# pcm5102_dac.net
KiCad netlist of a schematic drawn in EAGLE
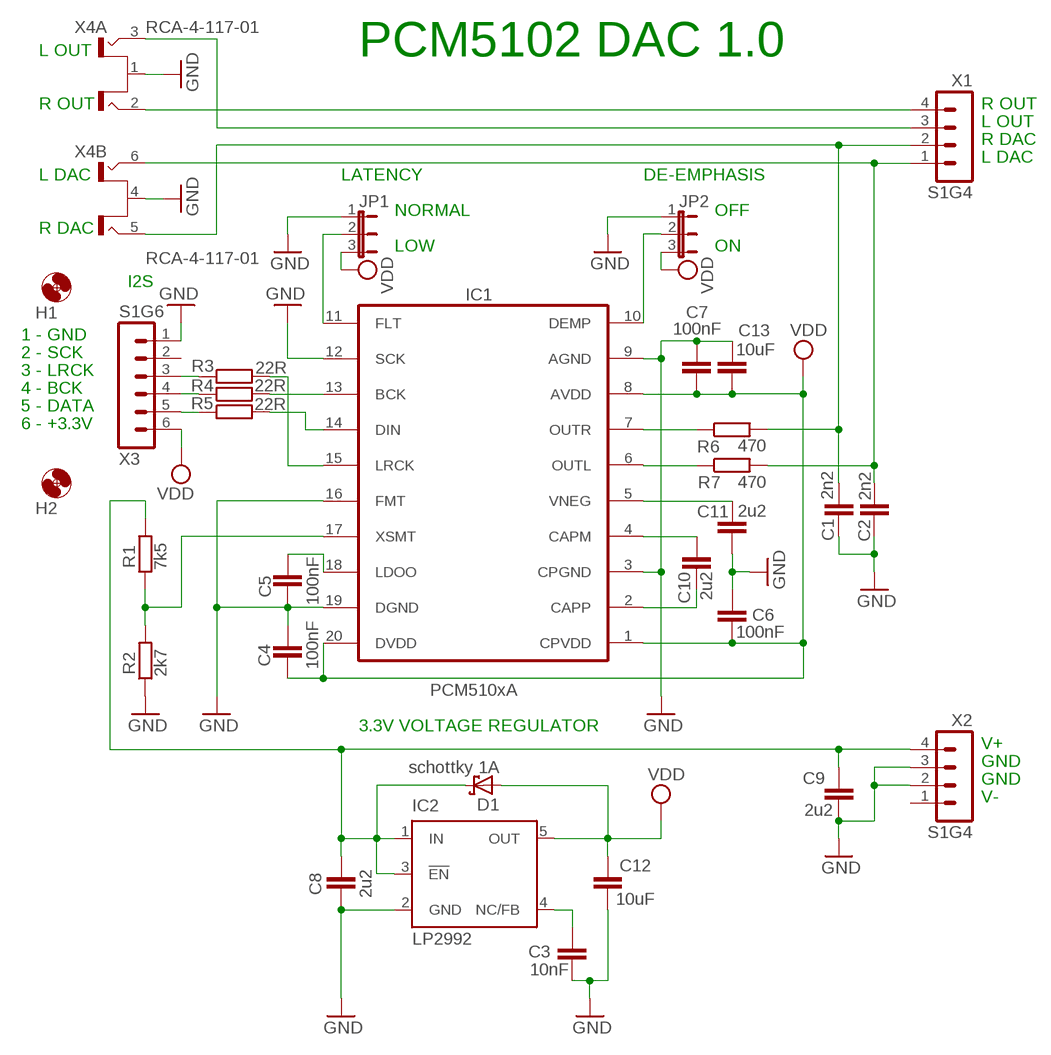
[diagram p0: schematic, sheet 1]

(export (version "E")
  (design (tool "Eeschema 10.0.6"))
  (components
    (comp (ref "C1")
      (value "2n2")
      (footprint "eagle-import:C1206")
      (libsource (lib "eagle-import") (part "C-EUC1206"))
    )
    (comp (ref "C2")
      (value "2n2")
      (footprint "eagle-import:C1206")
      (libsource (lib "eagle-import") (part "C-EUC1206"))
    )
    (comp (ref "C3")
      (value "10nF")
      (footprint "eagle-import:C1812")
      (libsource (lib "eagle-import") (part "C-EUC1812"))
    )
    (comp (ref "C4")
      (value "100nF")
      (footprint "eagle-import:C1206")
      (libsource (lib "eagle-import") (part "C-EUC1206"))
    )
    (comp (ref "C5")
      (value "100nF")
      (footprint "eagle-import:C1206")
      (libsource (lib "eagle-import") (part "C-EUC1206"))
    )
    (comp (ref "C6")
      (value "100nF")
      (footprint "eagle-import:C1206")
      (libsource (lib "eagle-import") (part "C-EUC1206"))
    )
    (comp (ref "C7")
      (value "100nF")
      (footprint "eagle-import:C1206")
      (libsource (lib "eagle-import") (part "C-EUC1206"))
    )
    (comp (ref "C8")
      (value "2u2")
      (footprint "eagle-import:C1206")
      (libsource (lib "eagle-import") (part "C-EUC1206"))
    )
    (comp (ref "C9")
      (value "2u2")
      (footprint "eagle-import:C1206")
      (libsource (lib "eagle-import") (part "C-EUC1206"))
    )
    (comp (ref "C10")
      (value "2u2")
      (footprint "eagle-import:C1206")
      (libsource (lib "eagle-import") (part "C-EUC1206"))
    )
    (comp (ref "C11")
      (value "2u2")
      (footprint "eagle-import:C1206")
      (libsource (lib "eagle-import") (part "C-EUC1206"))
    )
    (comp (ref "C12")
      (value "10uF")
      (footprint "eagle-import:C1206")
      (libsource (lib "eagle-import") (part "C-EUC1206"))
    )
    (comp (ref "C13")
      (value "10uF")
      (footprint "eagle-import:C1206")
      (libsource (lib "eagle-import") (part "C-EUC1206"))
    )
    (comp (ref "D1")
      (value "schottky 1A")
      (footprint "eagle-import:SMB")
      (libsource (lib "eagle-import") (part "SCHOTTKY-DIODESMD"))
    )
    (comp (ref "H1")
      (value "MOUNT-HOLE3.2")
      (footprint "eagle-import:3,2")
      (libsource (lib "eagle-import") (part "MOUNT-HOLE3.2"))
    )
    (comp (ref "H2")
      (value "MOUNT-HOLE3.2")
      (footprint "eagle-import:3,2")
      (libsource (lib "eagle-import") (part "MOUNT-HOLE3.2"))
    )
    (comp (ref "IC1")
      (value "PCM510xA")
      (footprint "eagle-import:TSSOP20")
      (libsource (lib "eagle-import") (part "PCM510X"))
    )
    (comp (ref "IC2")
      (value "LP2992")
      (footprint "eagle-import:SOT23-DBV")
      (fields (field (name "MF") "TEXAS INSTRUMENTS") (field (name "MPN") "TPS77001DBVT"))
      (libsource (lib "eagle-import") (part "TPS77001"))
    )
    (comp (ref "JP1")
      (value "DIL")
      (footprint "eagle-import:JP2")
      (libsource (lib "eagle-import") (part "JP2E"))
    )
    (comp (ref "JP2")
      (value "DIL")
      (footprint "eagle-import:JP2")
      (libsource (lib "eagle-import") (part "JP2E"))
    )
    (comp (ref "R1")
      (value "7k5")
      (footprint "eagle-import:R1206")
      (libsource (lib "eagle-import") (part "R-EU_R1206"))
    )
    (comp (ref "R2")
      (value "2k7")
      (footprint "eagle-import:R1206")
      (libsource (lib "eagle-import") (part "R-EU_R1206"))
    )
    (comp (ref "R3")
      (value "22R")
      (footprint "eagle-import:R1206")
      (libsource (lib "eagle-import") (part "R-EU_R1206"))
    )
    (comp (ref "R4")
      (value "22R")
      (footprint "eagle-import:R1206")
      (libsource (lib "eagle-import") (part "R-EU_R1206"))
    )
    (comp (ref "R5")
      (value "22R")
      (footprint "eagle-import:R1206")
      (libsource (lib "eagle-import") (part "R-EU_R1206"))
    )
    (comp (ref "R6")
      (value "470")
      (footprint "eagle-import:R1206")
      (libsource (lib "eagle-import") (part "R-EU_R1206"))
    )
    (comp (ref "R7")
      (value "470")
      (footprint "eagle-import:R1206")
      (libsource (lib "eagle-import") (part "R-EU_R1206"))
    )
    (comp (ref "X1")
      (value "S1G4")
      (footprint "eagle-import:MA04-1")
      (libsource (lib "eagle-import") (part "MA04-1"))
    )
    (comp (ref "X2")
      (value "S1G4")
      (footprint "eagle-import:MA04-1")
      (libsource (lib "eagle-import") (part "MA04-1"))
    )
    (comp (ref "X3")
      (value "S1G6")
      (footprint "eagle-import:MA06-1")
      (libsource (lib "eagle-import") (part "MA06-1"))
    )
    (comp (ref "X4")
      (value "RCA-4-117-01")
      (footprint "eagle-import:RCA-4-117-01")
      (libsource (lib "eagle-import") (part "RCA-4-117-01"))
    )
  )
  (nets
    (net (code "1") (name "GND") (class "Default")
      (node (ref "C1") (pin "2") (pinfunction "2_2") (pintype "passive"))
      (node (ref "C11") (pin "2") (pinfunction "2_2") (pintype "passive"))
      (node (ref "C12") (pin "2") (pinfunction "2_2") (pintype "passive"))
      (node (ref "C13") (pin "1") (pinfunction "1_1") (pintype "passive"))
      (node (ref "C2") (pin "2") (pinfunction "2_2") (pintype "passive"))
      (node (ref "C3") (pin "2") (pinfunction "2_2") (pintype "passive"))
      (node (ref "C4") (pin "1") (pinfunction "1_1") (pintype "passive"))
      (node (ref "C5") (pin "2") (pinfunction "2_2") (pintype "passive"))
      (node (ref "C6") (pin "1") (pinfunction "1_1") (pintype "passive"))
      (node (ref "C7") (pin "1") (pinfunction "1_1") (pintype "passive"))
      (node (ref "C8") (pin "2") (pinfunction "2_2") (pintype "passive"))
      (node (ref "C9") (pin "2") (pinfunction "2_2") (pintype "passive"))
      (node (ref "IC1") (pin "12") (pinfunction "SCK_12") (pintype "input"))
      (node (ref "IC1") (pin "16") (pinfunction "FMT_16") (pintype "input"))
      (node (ref "IC1") (pin "19") (pinfunction "DGND_19") (pintype "power_in"))
      (node (ref "IC1") (pin "3") (pinfunction "CPGND_3") (pintype "power_in"))
      (node (ref "IC1") (pin "9") (pinfunction "AGND_9") (pintype "power_in"))
      (node (ref "IC2") (pin "2") (pinfunction "GND_2") (pintype "power_in"))
      (node (ref "JP1") (pin "1") (pinfunction "1_1") (pintype "passive"))
      (node (ref "JP2") (pin "1") (pinfunction "1_1") (pintype "passive"))
      (node (ref "R2") (pin "1") (pinfunction "1_1") (pintype "passive"))
      (node (ref "X2") (pin "2") (pinfunction "2_2") (pintype "passive"))
      (node (ref "X2") (pin "3") (pinfunction "3_3") (pintype "passive"))
      (node (ref "X3") (pin "1") (pinfunction "1_1") (pintype "passive"))
      (node (ref "X4") (pin "1") (pinfunction "S_1") (pintype "passive"))
      (node (ref "X4") (pin "4") (pinfunction "S_4") (pintype "passive"))
    )
    (net (code "2") (name "Net-(IC1-BCK)") (class "Default")
      (node (ref "IC1") (pin "13") (pinfunction "BCK_13") (pintype "input"))
      (node (ref "R4") (pin "2") (pinfunction "2_2") (pintype "passive"))
    )
    (net (code "3") (name "Net-(IC1-CAPM)") (class "Default")
      (node (ref "C10") (pin "1") (pinfunction "1_1") (pintype "passive"))
      (node (ref "IC1") (pin "4") (pinfunction "CAPM_4") (pintype "output"))
    )
    (net (code "4") (name "Net-(IC1-CAPP)") (class "Default")
      (node (ref "C10") (pin "2") (pinfunction "2_2") (pintype "passive"))
      (node (ref "IC1") (pin "2") (pinfunction "CAPP_2") (pintype "output"))
    )
    (net (code "5") (name "Net-(IC1-DEMP)") (class "Default")
      (node (ref "IC1") (pin "10") (pinfunction "DEMP_10") (pintype "input"))
      (node (ref "JP2") (pin "2") (pinfunction "2_2") (pintype "passive"))
    )
    (net (code "6") (name "Net-(IC1-DIN)") (class "Default")
      (node (ref "IC1") (pin "14") (pinfunction "DIN_14") (pintype "input"))
      (node (ref "R5") (pin "2") (pinfunction "2_2") (pintype "passive"))
    )
    (net (code "7") (name "Net-(IC1-FLT)") (class "Default")
      (node (ref "IC1") (pin "11") (pinfunction "FLT_11") (pintype "input"))
      (node (ref "JP1") (pin "2") (pinfunction "2_2") (pintype "passive"))
    )
    (net (code "8") (name "Net-(IC1-LDOO)") (class "Default")
      (node (ref "C5") (pin "1") (pinfunction "1_1") (pintype "passive"))
      (node (ref "IC1") (pin "18") (pinfunction "LDOO_18") (pintype "power_in"))
    )
    (net (code "9") (name "Net-(IC1-LRCK)") (class "Default")
      (node (ref "IC1") (pin "15") (pinfunction "LRCK_15") (pintype "input"))
      (node (ref "R3") (pin "2") (pinfunction "2_2") (pintype "passive"))
    )
    (net (code "10") (name "Net-(IC1-OUTL)") (class "Default")
      (node (ref "IC1") (pin "6") (pinfunction "OUTL_6") (pintype "output"))
      (node (ref "R7") (pin "1") (pinfunction "1_1") (pintype "passive"))
    )
    (net (code "11") (name "Net-(IC1-OUTR)") (class "Default")
      (node (ref "IC1") (pin "7") (pinfunction "OUTR_7") (pintype "output"))
      (node (ref "R6") (pin "1") (pinfunction "1_1") (pintype "passive"))
    )
    (net (code "12") (name "Net-(IC1-VNEG)") (class "Default")
      (node (ref "C11") (pin "1") (pinfunction "1_1") (pintype "passive"))
      (node (ref "IC1") (pin "5") (pinfunction "VNEG_5") (pintype "output"))
    )
    (net (code "13") (name "Net-(IC1-XSMT)") (class "Default")
      (node (ref "IC1") (pin "17") (pinfunction "XSMT_17") (pintype "input"))
      (node (ref "R1") (pin "1") (pinfunction "1_1") (pintype "passive"))
      (node (ref "R2") (pin "2") (pinfunction "2_2") (pintype "passive"))
    )
    (net (code "14") (name "Net-(IC2-IN)") (class "Default")
      (node (ref "C8") (pin "1") (pinfunction "1_1") (pintype "passive"))
      (node (ref "C9") (pin "1") (pinfunction "1_1") (pintype "passive"))
      (node (ref "D1") (pin "C") (pinfunction "C_C") (pintype "passive"))
      (node (ref "IC2") (pin "1") (pinfunction "IN_1") (pintype "input"))
      (node (ref "IC2") (pin "3") (pinfunction "~{EN}_3") (pintype "input"))
      (node (ref "R1") (pin "2") (pinfunction "2_2") (pintype "passive"))
      (node (ref "X2") (pin "4") (pinfunction "4_4") (pintype "passive"))
    )
    (net (code "15") (name "Net-(IC2-NC{slash}FB)") (class "Default")
      (node (ref "C3") (pin "1") (pinfunction "1_1") (pintype "passive"))
      (node (ref "IC2") (pin "4") (pinfunction "NC/FB_4") (pintype "passive"))
    )
    (net (code "16") (name "Net-(R3-Pad1)") (class "Default")
      (node (ref "R3") (pin "1") (pinfunction "1_1") (pintype "passive"))
      (node (ref "X3") (pin "3") (pinfunction "3_3") (pintype "passive"))
    )
    (net (code "17") (name "Net-(R4-Pad1)") (class "Default")
      (node (ref "R4") (pin "1") (pinfunction "1_1") (pintype "passive"))
      (node (ref "X3") (pin "4") (pinfunction "4_4") (pintype "passive"))
    )
    (net (code "18") (name "Net-(R5-Pad1)") (class "Default")
      (node (ref "R5") (pin "1") (pinfunction "1_1") (pintype "passive"))
      (node (ref "X3") (pin "5") (pinfunction "5_5") (pintype "passive"))
    )
    (net (code "19") (name "Net-(X4A-T1)") (class "Default")
      (node (ref "X1") (pin "4") (pinfunction "4_4") (pintype "passive"))
      (node (ref "X4") (pin "2") (pinfunction "T1_2") (pintype "passive"))
    )
    (net (code "20") (name "Net-(X4A-T2)") (class "Default")
      (node (ref "X1") (pin "3") (pinfunction "3_3") (pintype "passive"))
      (node (ref "X4") (pin "3") (pinfunction "T2_3") (pintype "passive"))
    )
    (net (code "21") (name "Net-(X4B-T1)") (class "Default")
      (node (ref "C1") (pin "1") (pinfunction "1_1") (pintype "passive"))
      (node (ref "R6") (pin "2") (pinfunction "2_2") (pintype "passive"))
      (node (ref "X1") (pin "2") (pinfunction "2_2") (pintype "passive"))
      (node (ref "X4") (pin "5") (pinfunction "T1_5") (pintype "passive"))
    )
    (net (code "22") (name "Net-(X4B-T2)") (class "Default")
      (node (ref "C2") (pin "1") (pinfunction "1_1") (pintype "passive"))
      (node (ref "R7") (pin "2") (pinfunction "2_2") (pintype "passive"))
      (node (ref "X1") (pin "1") (pinfunction "1_1") (pintype "passive"))
      (node (ref "X4") (pin "6") (pinfunction "T2_6") (pintype "passive"))
    )
    (net (code "23") (name "VDD") (class "Default")
      (node (ref "C12") (pin "1") (pinfunction "1_1") (pintype "passive"))
      (node (ref "C13") (pin "2") (pinfunction "2_2") (pintype "passive"))
      (node (ref "C4") (pin "2") (pinfunction "2_2") (pintype "passive"))
      (node (ref "C6") (pin "2") (pinfunction "2_2") (pintype "passive"))
      (node (ref "C7") (pin "2") (pinfunction "2_2") (pintype "passive"))
      (node (ref "D1") (pin "A") (pinfunction "A_A") (pintype "passive"))
      (node (ref "IC1") (pin "1") (pinfunction "CPVDD_1") (pintype "power_in"))
      (node (ref "IC1") (pin "20") (pinfunction "DVDD_20") (pintype "power_in"))
      (node (ref "IC1") (pin "8") (pinfunction "AVDD_8") (pintype "power_in"))
      (node (ref "IC2") (pin "5") (pinfunction "OUT_5") (pintype "passive"))
      (node (ref "JP1") (pin "3") (pinfunction "3_3") (pintype "passive"))
      (node (ref "JP2") (pin "3") (pinfunction "3_3") (pintype "passive"))
      (node (ref "X3") (pin "6") (pinfunction "6_6") (pintype "passive"))
    )
    (net (code "24") (name "unconnected-(X2-Pad1)") (class "Default")
      (node (ref "X2") (pin "1") (pinfunction "1_1") (pintype "passive"))
    )
    (net (code "25") (name "unconnected-(X3-Pad2)") (class "Default")
      (node (ref "X3") (pin "2") (pinfunction "2_2") (pintype "passive"))
    )
  )
)
